# USB3.net
KiCad netlist of a schematic drawn in Altium Designer
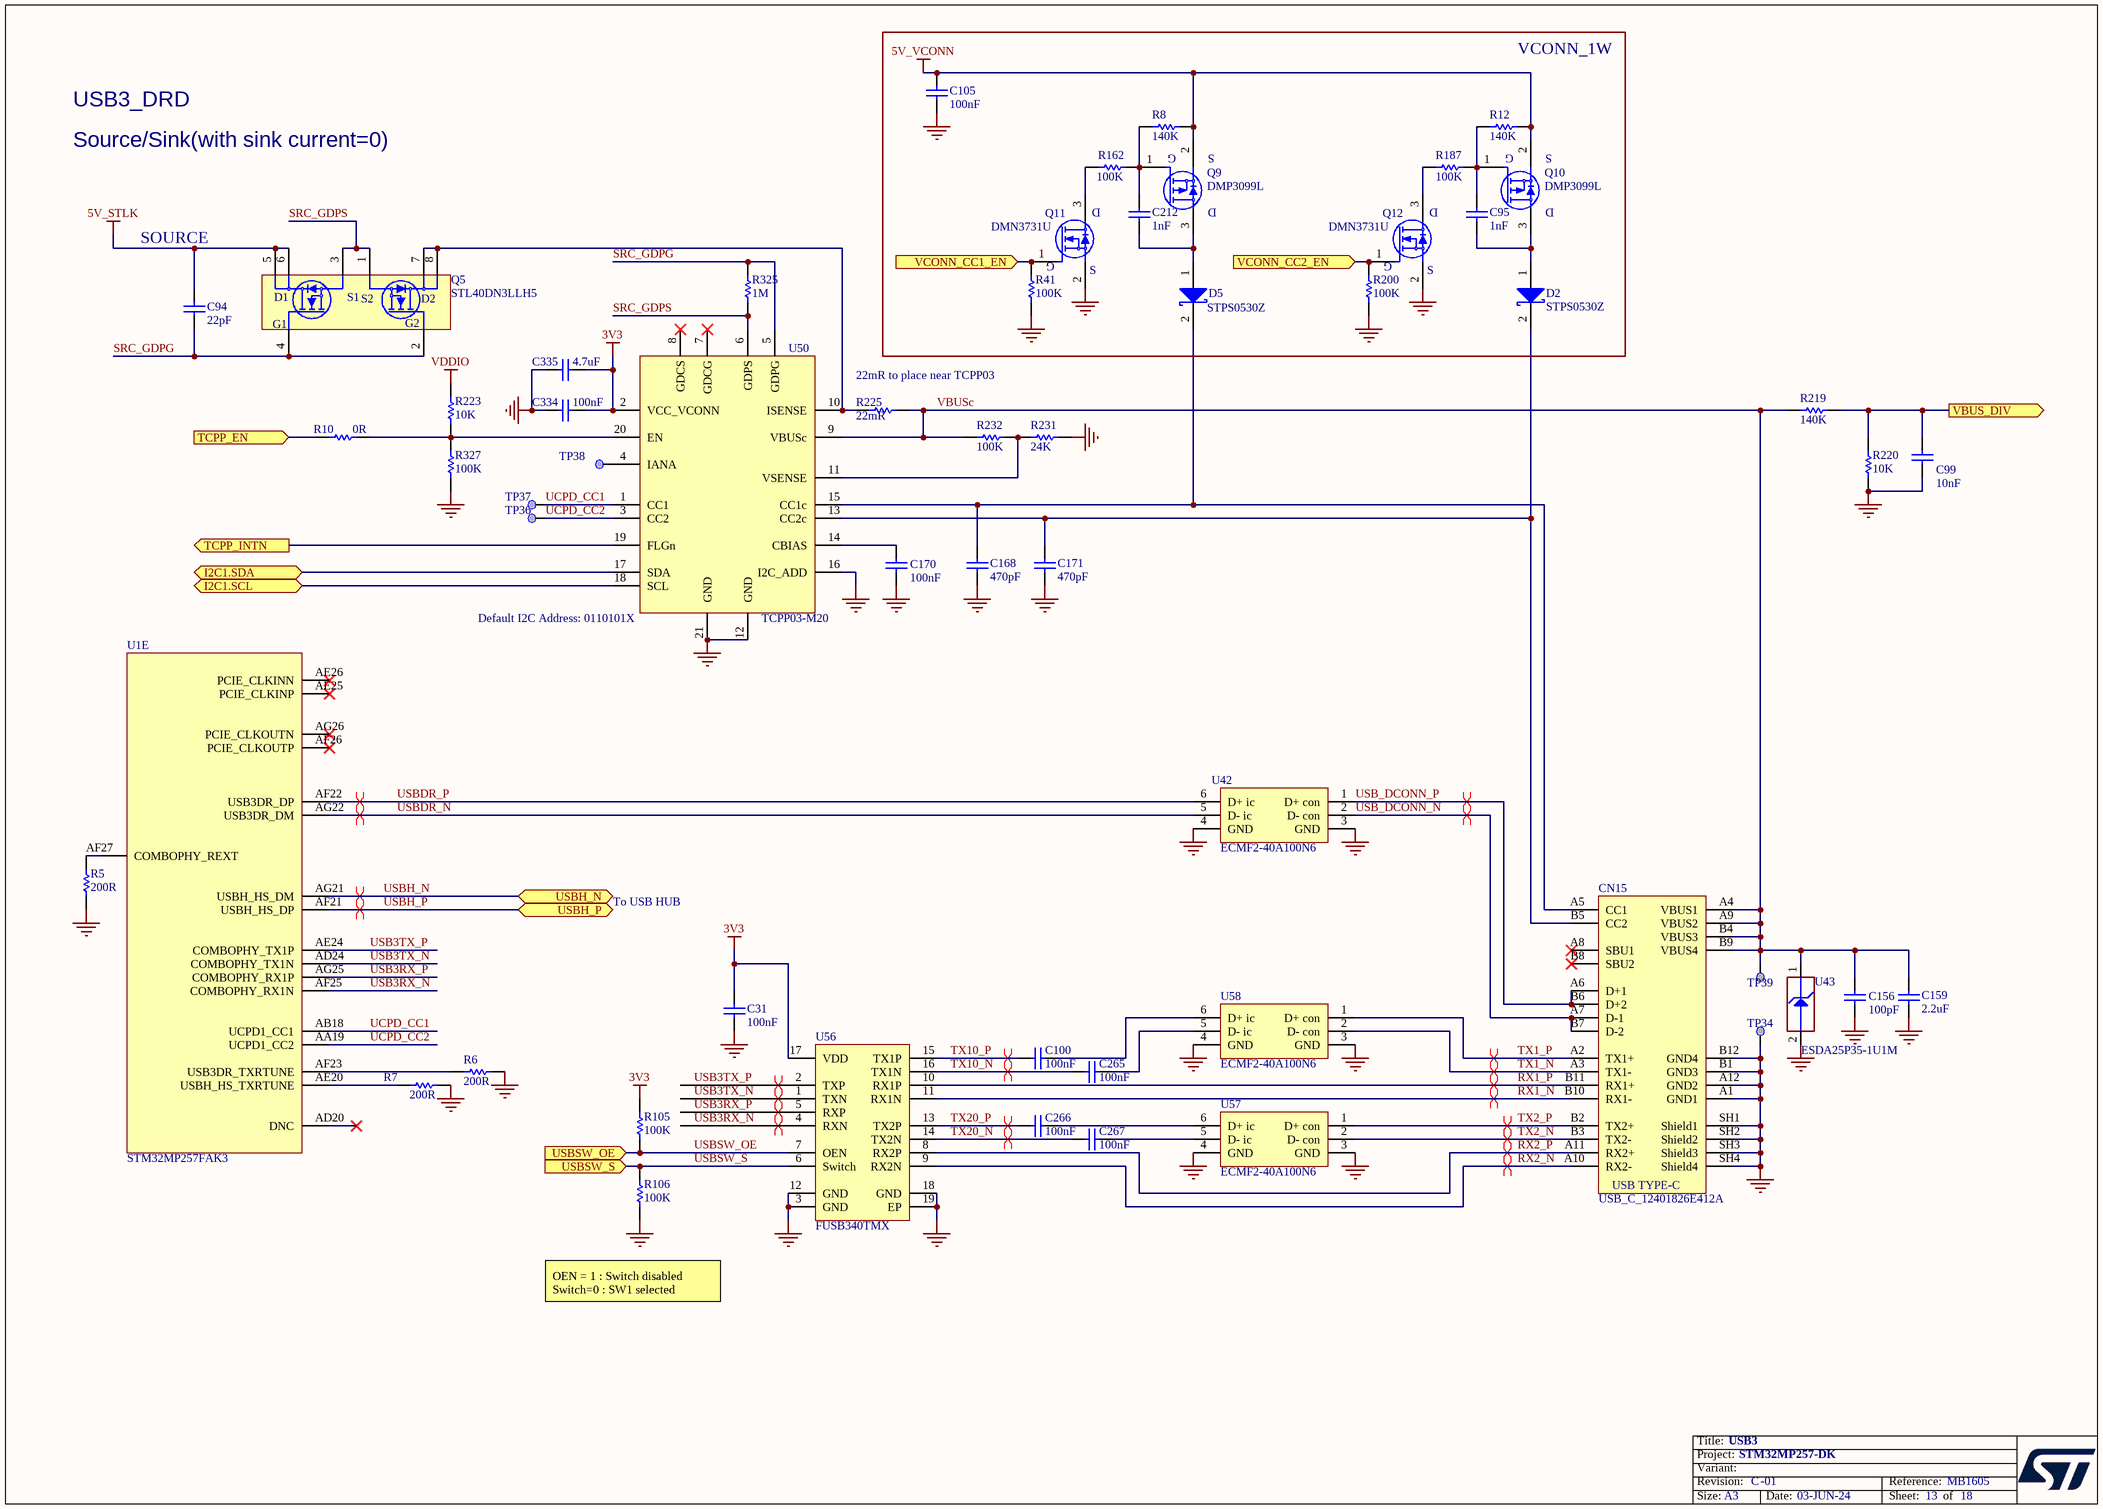
[diagram p0: USB3.SchDoc]

(export (version "E")
  (design (tool "Eeschema 10.0.6"))
  (components
    (comp (ref "C31")
      (value "100nF")
      (footprint "C0402")
      (description "Capacitor, MLCC, 100nF, 16V, X7R, +/-10%, 0402, T=0.5mm")
      (fields (field (name "INTERNAL_PART_NUMBER") "MCD-00006") (field (name "MANUFACTURER") "YAGEO"))
      (libsource (lib "MCD_PARTS_database") (part "Capacitor"))
    )
    (comp (ref "C94")
      (value "22pF")
      (footprint "C0402")
      (description "Capacitor, MLCC, 22pF, 50V, C0G, +/-5%, 0402, T=0.5mm")
      (fields (field (name "INTERNAL_PART_NUMBER") "MCD-01995") (field (name "MANUFACTURER") "TDK"))
      (libsource (lib "MCD_PARTS_database") (part "Capacitor"))
    )
    (comp (ref "C95")
      (value "1nF")
      (footprint "C0402")
      (description "Capacitor, MLCC, 1nF, 16V, X7R, +/-10%, 0402, T=0.5mm")
      (fields (field (name "INTERNAL_PART_NUMBER") "MCD-00198") (field (name "MANUFACTURER") "YAGEO"))
      (libsource (lib "MCD_PARTS_database") (part "Capacitor"))
    )
    (comp (ref "C99")
      (value "10nF")
      (footprint "C0402")
      (description "Capacitor, MLCC, 10nF, 16V, X7R, 10%, 0402, T=0.5mm")
      (fields
        (field (name "INTERNAL_PART_NUMBER") "MCD-00011")
        (field (name "MANUFACTURER_PART_NUMBER") "CC0402KRX7R7BB103")
        (field (name "PROVIDED_BY") "SUBCO")
      )
      (libsource (lib "MCD_PARTS_database") (part "Capacitor"))
    )
    (comp (ref "C100")
      (value "100nF")
      (footprint "C0201_H0P3")
      (description "Capacitor, MLCC, 100nF,10V, X5R, +/-10%, 0201, T=0.3mm")
      (fields (field (name "INTERNAL_PART_NUMBER") "MCD-00697") (field (name "MANUFACTURER") "TDK"))
      (libsource (lib "MCD_PARTS_database") (part "Capacitor"))
    )
    (comp (ref "C105")
      (value "100nF")
      (footprint "C0402")
      (description "Capacitor, MLCC, 100nF, 16V, X7R, +/-10%, 0402, T=0.5mm")
      (fields (field (name "INTERNAL_PART_NUMBER") "MCD-00006") (field (name "MANUFACTURER") "YAGEO"))
      (libsource (lib "MCD_PARTS_database") (part "Capacitor"))
    )
    (comp (ref "C156")
      (value "100pF")
      (footprint "C0402")
      (description "Capacitor, MLCC, 100pF, 50V, NPO, +/-5%, 0402, T=0.5mm")
      (fields
        (field (name "INTERNAL_PART_NUMBER") "MCD-00205")
        (field (name "MANUFACTURER_PART_NUMBER") "CC0402JRNPO9BN101")
      )
      (libsource (lib "MCD_PARTS_database") (part "Capacitor"))
    )
    (comp (ref "C159")
      (value "2.2uF")
      (footprint "C0805")
      (description "Capacitor, MLCC, 2.2uF, 25V, X7R, +/-10%, 0805, T=1,25mm")
      (fields (field (name "INTERNAL_PART_NUMBER") "MCD-02372") (field (name "MANUFACTURER") "MURATA"))
      (libsource (lib "MCD_PARTS_database") (part "Capacitor"))
    )
    (comp (ref "C168")
      (value "470pF")
      (footprint "C0402")
      (description "Capacitor, MLCC, 470pF, 50V, NPO, +/-5%, 0402, T=0.5mm")
      (fields
        (field (name "INTERNAL_PART_NUMBER") "MCD-00724")
        (field (name "MANUFACTURER_PART_NUMBER") "CC0402JRNPO9BN471")
      )
      (libsource (lib "MCD_PARTS_database") (part "Capacitor"))
    )
    (comp (ref "C170")
      (value "100nF")
      (footprint "C0603")
      (description "Capacitor, MLCC, 100nF, 50V, X7R, +/-10%, 0603, T=0.8mm")
      (fields (field (name "INTERNAL_PART_NUMBER") "MCD-01099") (field (name "BMS_PART_NUMBER") "9142278"))
      (libsource (lib "MCD_PARTS_database") (part "Capacitor"))
    )
    (comp (ref "C171")
      (value "470pF")
      (footprint "C0402")
      (description "Capacitor, MLCC, 470pF, 50V, NPO, +/-5%, 0402, T=0.5mm")
      (fields
        (field (name "INTERNAL_PART_NUMBER") "MCD-00724")
        (field (name "MANUFACTURER_PART_NUMBER") "CC0402JRNPO9BN471")
      )
      (libsource (lib "MCD_PARTS_database") (part "Capacitor"))
    )
    (comp (ref "C212")
      (value "1nF")
      (footprint "C0402")
      (description "Capacitor, MLCC, 1nF, 16V, X7R, +/-10%, 0402, T=0.5mm")
      (fields (field (name "INTERNAL_PART_NUMBER") "MCD-00198") (field (name "MANUFACTURER") "YAGEO"))
      (libsource (lib "MCD_PARTS_database") (part "Capacitor"))
    )
    (comp (ref "C265")
      (value "100nF")
      (footprint "C0201_H0P3")
      (description "Capacitor, MLCC, 100nF,10V, X5R, +/-10%, 0201, T=0.3mm")
      (fields (field (name "INTERNAL_PART_NUMBER") "MCD-00697") (field (name "MANUFACTURER") "TDK"))
      (libsource (lib "MCD_PARTS_database") (part "Capacitor"))
    )
    (comp (ref "C266")
      (value "100nF")
      (footprint "C0201_H0P3")
      (description "Capacitor, MLCC, 100nF,10V, X5R, +/-10%, 0201, T=0.3mm")
      (fields (field (name "INTERNAL_PART_NUMBER") "MCD-00697") (field (name "MANUFACTURER") "TDK"))
      (libsource (lib "MCD_PARTS_database") (part "Capacitor"))
    )
    (comp (ref "C267")
      (value "100nF")
      (footprint "C0201_H0P3")
      (description "Capacitor, MLCC, 100nF,10V, X5R, +/-10%, 0201, T=0.3mm")
      (fields (field (name "INTERNAL_PART_NUMBER") "MCD-00697") (field (name "MANUFACTURER") "TDK"))
      (libsource (lib "MCD_PARTS_database") (part "Capacitor"))
    )
    (comp (ref "C334")
      (value "100nF")
      (footprint "C0402")
      (description "Capacitor, MLCC, 100nF, 16V, X7R, +/-10%, 0402, T=0.5mm")
      (fields (field (name "INTERNAL_PART_NUMBER") "MCD-00006") (field (name "MANUFACTURER") "YAGEO"))
      (libsource (lib "MCD_PARTS_database") (part "Capacitor"))
    )
    (comp (ref "C335")
      (value "4.7uF")
      (footprint "C0402")
      (description "Capacitor, MLCC, 4.7uF, 6V3, X5R, +/-20%, 0402, T=0.5mm")
      (fields (field (name "INTERNAL_PART_NUMBER") "MCD-01356") (field (name "MANUFACTURER") "MURATA"))
      (libsource (lib "MCD_PARTS_database") (part "Capacitor"))
    )
    (comp (ref "CN15")
      (value "USB_C_12401826E412A")
      (footprint "CON_USB-TYPEC_AMPHENOL_12401826E412A")
      (description "USB_TypeC, 24 pins, RA, SMD, T=2.96mm (USB Certified 3.1)")
      (fields (field (name "INTERNAL_PART_NUMBER") "MCD-03232") (field (name "MANUFACTURER") "AMPHENOL ICC"))
      (libsource (lib "MCD_PARTS_database") (part "USB_TYPE_C_Receptacle"))
    )
    (comp (ref "D2")
      (value "STPS0530Z")
      (footprint "DIO_SOD123_1A_2K_H1P45")
      (description "Diode, Schottky, 0V33, 0.5A , 30V, SOD123")
      (fields
        (field (name "INTERNAL_PART_NUMBER") "MCD-03688")
        (field (name "MANUFACTURER") "STMICROELECTRONICS")
      )
      (libsource (lib "MCD_PARTS_database") (part "SCHOTTKY_1A_2K"))
    )
    (comp (ref "D5")
      (value "STPS0530Z")
      (footprint "DIO_SOD123_1A_2K_H1P45")
      (description "Diode, Schottky, 0V33, 0.5A , 30V, SOD123")
      (fields
        (field (name "INTERNAL_PART_NUMBER") "MCD-03688")
        (field (name "MANUFACTURER") "STMICROELECTRONICS")
      )
      (libsource (lib "MCD_PARTS_database") (part "SCHOTTKY_1A_2K"))
    )
    (comp (ref "Q5")
      (value "STL40DN3LLH5")
      (footprint "PowerFLAT_5x6")
      (description "MOSFET, Dual N-channel 30 V, 0.016 Ω typ., 40 A, STripFET™ H5 Power MOSFET")
      (fields
        (field (name "INTERNAL_PART_NUMBER") "MCD-02152")
        (field (name "MANUFACTURER") "STMICROELECTRONICS")
      )
      (libsource (lib "MCD_PARTS_database") (part "STL40DN3LLH5"))
    )
    (comp (ref "Q9")
      (value "DMP3099L")
      (footprint "MOS_SOT23")
      (description "Transistor, MOSFET, P-CH, 30V, 3.8A, SOT23")
      (fields
        (field (name "INTERNAL_PART_NUMBER") "MCD-03690")
        (field (name "MANUFACTURER") "DIODES INCORPORATED")
      )
      (libsource (lib "MCD_PARTS_database") (part "MOSFET_P-CHANNEL"))
    )
    (comp (ref "Q10")
      (value "DMP3099L")
      (footprint "MOS_SOT23")
      (description "Transistor, MOSFET, P-CH, 30V, 3.8A, SOT23")
      (fields
        (field (name "INTERNAL_PART_NUMBER") "MCD-03690")
        (field (name "MANUFACTURER") "DIODES INCORPORATED")
      )
      (libsource (lib "MCD_PARTS_database") (part "MOSFET_P-CHANNEL"))
    )
    (comp (ref "Q11")
      (value "DMN3731U")
      (footprint "MOS_SOT23")
      (description "Transistor, MOSFET, N-CH, 30V, 0.9A, SOT23")
      (fields
        (field (name "INTERNAL_PART_NUMBER") "MCD-03691")
        (field (name "MANUFACTURER") "DIODES INCORPORATED")
      )
      (libsource (lib "MCD_PARTS_database") (part "MOSFET_N-CHANNEL"))
    )
    (comp (ref "Q12")
      (value "DMN3731U")
      (footprint "MOS_SOT23")
      (description "Transistor, MOSFET, N-CH, 30V, 0.9A, SOT23")
      (fields
        (field (name "INTERNAL_PART_NUMBER") "MCD-03691")
        (field (name "MANUFACTURER") "DIODES INCORPORATED")
      )
      (libsource (lib "MCD_PARTS_database") (part "MOSFET_N-CHANNEL"))
    )
    (comp (ref "R5")
      (value "200R")
      (footprint "R0402")
      (description "Resistor, 200R, 0402, +/-1%, 1/16W")
      (fields (field (name "INTERNAL_PART_NUMBER") "MCD-00417") (field (name "MANUFACTURER") "YAGEO"))
      (libsource (lib "MCD_PARTS_database") (part "Resistor"))
    )
    (comp (ref "R6")
      (value "200R")
      (footprint "R0402")
      (description "Resistor, 200R, 0402, +/-1%, 1/16W")
      (fields (field (name "INTERNAL_PART_NUMBER") "MCD-00417") (field (name "MANUFACTURER") "YAGEO"))
      (libsource (lib "MCD_PARTS_database") (part "Resistor"))
    )
    (comp (ref "R7")
      (value "200R")
      (footprint "R0402")
      (description "Resistor, 200R, 0402, +/-1%, 1/16W")
      (fields (field (name "INTERNAL_PART_NUMBER") "MCD-00417") (field (name "MANUFACTURER") "YAGEO"))
      (libsource (lib "MCD_PARTS_database") (part "Resistor"))
    )
    (comp (ref "R8")
      (value "140K")
      (footprint "R0402")
      (description "Resistor, 140K, 0402, +/-1%, 1/16W")
      (fields (field (name "INTERNAL_PART_NUMBER") "MCD-02335") (field (name "MANUFACTURER") "YAGEO"))
      (libsource (lib "MCD_PARTS_database") (part "Resistor"))
    )
    (comp (ref "R10")
      (value "0R")
      (footprint "R0402")
      (description "Resistor,0R,0402,5%,1/16W")
      (fields
        (field (name "INTERNAL_PART_NUMBER") "MCD-00052")
        (field (name "MANUFACTURER_PART_NUMBER") "RC0402JR-070RL")
      )
      (libsource (lib "MCD_PARTS_database") (part "Resistor"))
    )
    (comp (ref "R12")
      (value "140K")
      (footprint "R0402")
      (description "Resistor, 140K, 0402, +/-1%, 1/16W")
      (fields (field (name "INTERNAL_PART_NUMBER") "MCD-02335") (field (name "MANUFACTURER") "YAGEO"))
      (libsource (lib "MCD_PARTS_database") (part "Resistor"))
    )
    (comp (ref "R41")
      (value "100K")
      (footprint "R0402")
      (description "Resistor, 100K, 0402, +/-1%, 1/16W")
      (fields (field (name "INTERNAL_PART_NUMBER") "MCD-00059") (field (name "MANUFACTURER") "YAGEO"))
      (libsource (lib "MCD_PARTS_database") (part "Resistor"))
    )
    (comp (ref "R105")
      (value "100K")
      (footprint "R0402")
      (description "Resistor,100K,0402,1%,1/16W")
      (fields (field (name "INTERNAL_PART_NUMBER") "MCD-00059") (field (name "MANUFACTURER") "YAGEO"))
      (libsource (lib "MCD_PARTS_database") (part "Resistor"))
    )
    (comp (ref "R106")
      (value "100K")
      (footprint "R0402")
      (description "Resistor,100K,0402,1%,1/16W")
      (fields (field (name "INTERNAL_PART_NUMBER") "MCD-00059") (field (name "MANUFACTURER") "YAGEO"))
      (libsource (lib "MCD_PARTS_database") (part "Resistor"))
    )
    (comp (ref "R162")
      (value "100K")
      (footprint "R0402")
      (description "Resistor, 100K, 0402, +/-1%, 1/16W")
      (fields (field (name "INTERNAL_PART_NUMBER") "MCD-00059") (field (name "MANUFACTURER") "YAGEO"))
      (libsource (lib "MCD_PARTS_database") (part "Resistor"))
    )
    (comp (ref "R187")
      (value "100K")
      (footprint "R0402")
      (description "Resistor, 100K, 0402, +/-1%, 1/16W")
      (fields (field (name "INTERNAL_PART_NUMBER") "MCD-00059") (field (name "MANUFACTURER") "YAGEO"))
      (libsource (lib "MCD_PARTS_database") (part "Resistor"))
    )
    (comp (ref "R200")
      (value "100K")
      (footprint "R0402")
      (description "Resistor, 100K, 0402, +/-1%, 1/16W")
      (fields (field (name "INTERNAL_PART_NUMBER") "MCD-00059") (field (name "MANUFACTURER") "YAGEO"))
      (libsource (lib "MCD_PARTS_database") (part "Resistor"))
    )
    (comp (ref "R219")
      (value "140K")
      (footprint "R0402")
      (description "Resistor, 140K, 0402, +/-1%, 1/16W")
      (fields (field (name "INTERNAL_PART_NUMBER") "MCD-02335") (field (name "MANUFACTURER") "YAGEO"))
      (libsource (lib "MCD_PARTS_database") (part "Resistor"))
    )
    (comp (ref "R220")
      (value "10K")
      (footprint "R0402")
      (description "Resistor, 10K, 0402, +/-1%, 1/16W")
      (fields (field (name "INTERNAL_PART_NUMBER") "MCD-00053") (field (name "BMS_PART_NUMBER") "9131590"))
      (libsource (lib "MCD_PARTS_database") (part "Resistor"))
    )
    (comp (ref "R223")
      (value "10K")
      (footprint "R0402")
      (description "Resistor, 10K, 0402, +/-1%, 1/16W")
      (fields (field (name "INTERNAL_PART_NUMBER") "MCD-00053") (field (name "BMS_PART_NUMBER") "9131590"))
      (libsource (lib "MCD_PARTS_database") (part "Resistor"))
    )
    (comp (ref "R225")
      (value "22mR")
      (footprint "R0603")
      (description "Resistor, 22mR, 0603, +/-1%, 1/3W")
      (fields (field (name "INTERNAL_PART_NUMBER") "MCD-02232") (field (name "MANUFACTURER") "PANASONIC"))
      (libsource (lib "MCD_PARTS_database") (part "Resistor"))
    )
    (comp (ref "R231")
      (value "24K")
      (footprint "R0402")
      (description "Resistor, 24K, 0402, +/-1%, 1/16W")
      (fields (field (name "INTERNAL_PART_NUMBER") "MCD-00435") (field (name "MANUFACTURER") "YAGEO"))
      (libsource (lib "MCD_PARTS_database") (part "Resistor"))
    )
    (comp (ref "R232")
      (value "100K")
      (footprint "R0402")
      (description "Resistor,100K,0402,0.5%,1/16W")
      (fields (field (name "INTERNAL_PART_NUMBER") "MCD-02265") (field (name "MANUFACTURER") "YAGEO"))
      (libsource (lib "MCD_PARTS_database") (part "Resistor"))
    )
    (comp (ref "R325")
      (value "1M")
      (footprint "R0402")
      (description "Resistor, 1M, 0402, +/-1%, 1/16W")
      (fields (field (name "INTERNAL_PART_NUMBER") "MCD-00182") (field (name "BMS_PART_NUMBER") "9131778"))
      (libsource (lib "MCD_PARTS_database") (part "Resistor"))
    )
    (comp (ref "R327")
      (value "100K")
      (footprint "R0402")
      (description "Resistor,100K,0402,0.5%,1/16W")
      (fields (field (name "INTERNAL_PART_NUMBER") "MCD-02265") (field (name "MANUFACTURER") "YAGEO"))
      (libsource (lib "MCD_PARTS_database") (part "Resistor"))
    )
    (comp (ref "TP34")
      (value "Test Point")
      (footprint "TP_SMD_1MM")
      (description "Test Point 1mm")
      (fields
        (field (name "INTERNAL_PART_NUMBER") "MCD-00074")
        (field (name "MANUFACTURER_PART_NUMBER") "n/a")
      )
      (libsource (lib "") (part "Test Point_2"))
    )
    (comp (ref "TP36")
      (value "Test Point")
      (footprint "TP_SMD_1MM")
      (description "Test Point 1mm")
      (fields
        (field (name "INTERNAL_PART_NUMBER") "MCD-00074")
        (field (name "MANUFACTURER_PART_NUMBER") "n/a")
      )
      (libsource (lib "MCD_PARTS_database") (part "Test Point"))
    )
    (comp (ref "TP37")
      (value "Test Point")
      (footprint "TP_SMD_1MM")
      (description "Test Point 1mm")
      (fields
        (field (name "INTERNAL_PART_NUMBER") "MCD-00074")
        (field (name "MANUFACTURER_PART_NUMBER") "n/a")
      )
      (libsource (lib "MCD_PARTS_database") (part "Test Point"))
    )
    (comp (ref "TP38")
      (value "Test Point")
      (footprint "TP_SMD_1MM")
      (description "Test Point 1mm")
      (fields
        (field (name "INTERNAL_PART_NUMBER") "MCD-00074")
        (field (name "MANUFACTURER_PART_NUMBER") "n/a")
      )
      (libsource (lib "MCD_PARTS_database") (part "Test Point"))
    )
    (comp (ref "TP39")
      (value "Test Point")
      (footprint "TP_SMD_1MM")
      (description "Test Point 1mm")
      (fields
        (field (name "INTERNAL_PART_NUMBER") "MCD-00074")
        (field (name "MANUFACTURER_PART_NUMBER") "n/a")
      )
      (libsource (lib "") (part "Test Point_1"))
    )
    (comp (ref "U1")
      (value "STM32MP257FAK3")
      (footprint "ICC_TFBGA424_14X14_P050_H1P20_CODE-B0A2")
      (description "MPU , 2xCortex-A35@1.5GHz, Cortex-M33@400MHz, TFBGA 14x14, pitch 0.5, 648KB SRAM, With Crypto")
      (fields
        (field (name "INTERNAL_PART_NUMBER") "MCD-03375")
        (field (name "MANUFACTURER") "STMICROELECTRONICS")
      )
      (libsource (lib "MCD_PARTS_database") (part "STM32MP257FAK3"))
    )
    (comp (ref "U42")
      (value "ECMF2-40A100N6")
      (footprint "ESD_UQFN-6L_1P45X1P4_P040")
      (description "ESD protection & Common Filter High Speed serial Interfaces , 0.4 pitch")
      (fields
        (field (name "INTERNAL_PART_NUMBER") "MCD-03060")
        (field (name "MANUFACTURER") "STMICROELECTRONICS")
      )
      (libsource (lib "MCD_PARTS_database") (part "ECMF2-40A100N6"))
    )
    (comp (ref "U43")
      (value "ESDA25P35-1U1M")
      (footprint "ESD_QFN1610_2N_1K_2A")
      (description "High power Transient voltage suppressor:25V/35A EOS and ESD transients protection.")
      (fields (field (name "INTERNAL_PART_NUMBER") "MCD-01207") (field (name "BMS_PART_NUMBER") "9179045"))
      (libsource (lib "MCD_PARTS_database") (part "ESD-TRANSIL"))
    )
    (comp (ref "U50")
      (value "TCPP03-M20")
      (footprint "ICC_QFN20-EPAD_4X4_P050")
      (description "USB Type-C Port Protection for USB DRP Power Delivery, PPS compliant")
      (fields
        (field (name "INTERNAL_PART_NUMBER") "MCD-02130")
        (field (name "MANUFACTURER") "STMICROELECTRONICS")
      )
      (libsource (lib "MCD_PARTS_database") (part "TCPP03-M20"))
    )
    (comp (ref "U56")
      (value "FUSB340TMX")
      (footprint "ICC_UQFN18-EPAD_2X2P80_P040")
      (description "Switch USB3.1 Superspeed 10 Gbps , Gen1 and Gen2")
      (fields
        (field (name "INTERNAL_PART_NUMBER") "MCD-02300")
        (field (name "MANUFACTURER") "ON SEMICONDUCTOR")
      )
      (libsource (lib "MCD_PARTS_database") (part "FUSB340TMX"))
    )
    (comp (ref "U57")
      (value "ECMF2-40A100N6")
      (footprint "ESD_UQFN-6L_1P45X1P4_P040")
      (description "IC, ESD protection and Common Filter High Speed serial Interfaces, 10.7 GHz")
      (fields
        (field (name "INTERNAL_PART_NUMBER") "MCD-03060")
        (field (name "MANUFACTURER") "STMICROELECTRONICS")
      )
      (libsource (lib "MCD_PARTS_database") (part "ECMF2-40A100N6"))
    )
    (comp (ref "U58")
      (value "ECMF2-40A100N6")
      (footprint "ESD_UQFN-6L_1P45X1P4_P040")
      (description "IC, ESD protection and Common Filter High Speed serial Interfaces, 10.7 GHz")
      (fields
        (field (name "INTERNAL_PART_NUMBER") "MCD-03060")
        (field (name "MANUFACTURER") "STMICROELECTRONICS")
      )
      (libsource (lib "MCD_PARTS_database") (part "ECMF2-40A100N6"))
    )
  )
  (nets
    (net (code "1") (name "/I2C1.SCL") (class "Default")
      (node (ref "U50") (pin "18") (pinfunction "SCL_18") (pintype "passive"))
    )
    (net (code "2") (name "/I2C1.SDA") (class "Default")
      (node (ref "U50") (pin "17") (pinfunction "SDA_17") (pintype "passive"))
    )
    (net (code "3") (name "/RX1_N") (class "Default")
      (node (ref "CN15") (pin "B10") (pinfunction "RX1-_B10") (pintype "passive"))
      (node (ref "U56") (pin "11") (pinfunction "RX1N_11") (pintype "passive"))
    )
    (net (code "4") (name "/RX1_P") (class "Default")
      (node (ref "CN15") (pin "B11") (pinfunction "RX1+_B11") (pintype "passive"))
      (node (ref "U56") (pin "10") (pinfunction "RX1P_10") (pintype "passive"))
    )
    (net (code "5") (name "/RX2_N") (class "Default")
      (node (ref "CN15") (pin "A10") (pinfunction "RX2-_A10") (pintype "passive"))
      (node (ref "U56") (pin "9") (pinfunction "RX2N_9") (pintype "passive"))
    )
    (net (code "6") (name "/RX2_P") (class "Default")
      (node (ref "CN15") (pin "A11") (pinfunction "RX2+_A11") (pintype "passive"))
      (node (ref "U56") (pin "8") (pinfunction "RX2P_8") (pintype "passive"))
    )
    (net (code "7") (name "/SRC_GDPG") (class "Default")
      (node (ref "C94") (pin "1") (pinfunction "1_1") (pintype "passive"))
      (node (ref "Q5") (pin "2") (pinfunction "G2_2") (pintype "passive"))
      (node (ref "Q5") (pin "4") (pinfunction "G1_4") (pintype "passive"))
      (node (ref "R325") (pin "2") (pinfunction "2_2") (pintype "passive"))
      (node (ref "U50") (pin "5") (pinfunction "GDPG_5") (pintype "passive"))
    )
    (net (code "8") (name "/SRC_GDPS") (class "Default")
      (node (ref "Q5") (pin "1") (pinfunction "S2_1") (pintype "passive"))
      (node (ref "Q5") (pin "3") (pinfunction "S1_3") (pintype "passive"))
      (node (ref "R325") (pin "1") (pinfunction "1_1") (pintype "passive"))
      (node (ref "U50") (pin "6") (pinfunction "GDPS_6") (pintype "passive"))
    )
    (net (code "9") (name "/TCPP_EN") (class "Default")
      (node (ref "R10") (pin "1") (pinfunction "1_1") (pintype "passive"))
    )
    (net (code "10") (name "/TCPP_INTN") (class "Default")
      (node (ref "U50") (pin "19") (pinfunction "FLGn_19") (pintype "passive"))
    )
    (net (code "11") (name "/TX1_N") (class "Default")
      (node (ref "CN15") (pin "A3") (pinfunction "TX1-_A3") (pintype "passive"))
      (node (ref "U58") (pin "2") (pinfunction "D-_con_2") (pintype "passive"))
    )
    (net (code "12") (name "/TX1_P") (class "Default")
      (node (ref "CN15") (pin "A2") (pinfunction "TX1+_A2") (pintype "passive"))
      (node (ref "U58") (pin "1") (pinfunction "D+_con_1") (pintype "passive"))
    )
    (net (code "13") (name "/TX2_N") (class "Default")
      (node (ref "CN15") (pin "B3") (pinfunction "TX2-_B3") (pintype "passive"))
      (node (ref "U57") (pin "2") (pinfunction "D-_con_2") (pintype "passive"))
    )
    (net (code "14") (name "/TX2_P") (class "Default")
      (node (ref "CN15") (pin "B2") (pinfunction "TX2+_B2") (pintype "passive"))
      (node (ref "U57") (pin "1") (pinfunction "D+_con_1") (pintype "passive"))
    )
    (net (code "15") (name "/TX10_N") (class "Default")
      (node (ref "C265") (pin "1") (pinfunction "1_1") (pintype "passive"))
      (node (ref "U56") (pin "16") (pinfunction "TX1N_16") (pintype "passive"))
    )
    (net (code "16") (name "/TX10_P") (class "Default")
      (node (ref "C100") (pin "1") (pinfunction "1_1") (pintype "passive"))
      (node (ref "U56") (pin "15") (pinfunction "TX1P_15") (pintype "passive"))
    )
    (net (code "17") (name "/TX20_N") (class "Default")
      (node (ref "C267") (pin "1") (pinfunction "1_1") (pintype "passive"))
      (node (ref "U56") (pin "14") (pinfunction "TX2N_14") (pintype "passive"))
    )
    (net (code "18") (name "/TX20_P") (class "Default")
      (node (ref "C266") (pin "1") (pinfunction "1_1") (pintype "passive"))
      (node (ref "U56") (pin "13") (pinfunction "TX2P_13") (pintype "passive"))
    )
    (net (code "19") (name "/UCPD_CC1") (class "Default")
      (node (ref "TP37") (pin "1") (pinfunction "1_1") (pintype "passive"))
      (node (ref "U1") (pin "AB18") (pinfunction "UCPD1_CC1_AB18") (pintype "passive"))
      (node (ref "U50") (pin "1") (pinfunction "CC1_1") (pintype "passive"))
    )
    (net (code "20") (name "/UCPD_CC2") (class "Default")
      (node (ref "TP36") (pin "1") (pinfunction "1_1") (pintype "passive"))
      (node (ref "U1") (pin "AA19") (pinfunction "UCPD1_CC2_AA19") (pintype "passive"))
      (node (ref "U50") (pin "3") (pinfunction "CC2_3") (pintype "passive"))
    )
    (net (code "21") (name "/USB3RX_N") (class "Default")
      (node (ref "U1") (pin "AF25") (pinfunction "COMBOPHY_RX1N_AF25") (pintype "passive"))
      (node (ref "U56") (pin "4") (pinfunction "RXN_4") (pintype "passive"))
    )
    (net (code "22") (name "/USB3RX_P") (class "Default")
      (node (ref "U1") (pin "AG25") (pinfunction "COMBOPHY_RX1P_AG25") (pintype "passive"))
      (node (ref "U56") (pin "5") (pinfunction "RXP_5") (pintype "passive"))
    )
    (net (code "23") (name "/USB3TX_N") (class "Default")
      (node (ref "U1") (pin "AD24") (pinfunction "COMBOPHY_TX1N_AD24") (pintype "passive"))
      (node (ref "U56") (pin "1") (pinfunction "TXN_1") (pintype "passive"))
    )
    (net (code "24") (name "/USB3TX_P") (class "Default")
      (node (ref "U1") (pin "AE24") (pinfunction "COMBOPHY_TX1P_AE24") (pintype "passive"))
      (node (ref "U56") (pin "2") (pinfunction "TXP_2") (pintype "passive"))
    )
    (net (code "25") (name "/USBDR_N") (class "Default")
      (node (ref "U1") (pin "AG22") (pinfunction "USB3DR_DM_AG22") (pintype "passive"))
      (node (ref "U42") (pin "5") (pinfunction "D-_ic_5") (pintype "passive"))
    )
    (net (code "26") (name "/USBDR_P") (class "Default")
      (node (ref "U1") (pin "AF22") (pinfunction "USB3DR_DP_AF22") (pintype "passive"))
      (node (ref "U42") (pin "6") (pinfunction "D+_ic_6") (pintype "passive"))
    )
    (net (code "27") (name "/USBH_N") (class "Default")
      (node (ref "U1") (pin "AG21") (pinfunction "USBH_HS_DM_AG21") (pintype "passive"))
    )
    (net (code "28") (name "/USBH_P") (class "Default")
      (node (ref "U1") (pin "AF21") (pinfunction "USBH_HS_DP_AF21") (pintype "passive"))
    )
    (net (code "29") (name "/USBSW_OE") (class "Default")
      (node (ref "R105") (pin "1") (pinfunction "1_1") (pintype "passive"))
      (node (ref "U56") (pin "7") (pinfunction "OEN_7") (pintype "passive"))
    )
    (net (code "30") (name "/USBSW_S") (class "Default")
      (node (ref "R106") (pin "2") (pinfunction "2_2") (pintype "passive"))
      (node (ref "U56") (pin "6") (pinfunction "Switch_6") (pintype "passive"))
    )
    (net (code "31") (name "/USB_DCONN_N") (class "Default")
      (node (ref "CN15") (pin "A7") (pinfunction "D-1_A7") (pintype "passive"))
      (node (ref "CN15") (pin "B7") (pinfunction "D-2_B7") (pintype "passive"))
      (node (ref "U42") (pin "2") (pinfunction "D-_con_2") (pintype "passive"))
    )
    (net (code "32") (name "/USB_DCONN_P") (class "Default")
      (node (ref "CN15") (pin "A6") (pinfunction "D+1_A6") (pintype "passive"))
      (node (ref "CN15") (pin "B6") (pinfunction "D+2_B6") (pintype "passive"))
      (node (ref "U42") (pin "1") (pinfunction "D+_con_1") (pintype "passive"))
    )
    (net (code "33") (name "/VBUS_DIV") (class "Default")
      (node (ref "C99") (pin "1") (pinfunction "1_1") (pintype "passive"))
      (node (ref "R219") (pin "1") (pinfunction "1_1") (pintype "passive"))
      (node (ref "R220") (pin "2") (pinfunction "2_2") (pintype "passive"))
    )
    (net (code "34") (name "/VBUSc") (class "Default")
      (node (ref "C156") (pin "2") (pinfunction "2_2") (pintype "passive"))
      (node (ref "C159") (pin "2") (pinfunction "2_2") (pintype "passive"))
      (node (ref "CN15") (pin "A4") (pinfunction "VBUS1_A4") (pintype "passive"))
      (node (ref "CN15") (pin "A9") (pinfunction "VBUS2_A9") (pintype "passive"))
      (node (ref "CN15") (pin "B4") (pinfunction "VBUS3_B4") (pintype "passive"))
      (node (ref "CN15") (pin "B9") (pinfunction "VBUS4_B9") (pintype "passive"))
      (node (ref "R219") (pin "2") (pinfunction "2_2") (pintype "passive"))
      (node (ref "R225") (pin "1") (pinfunction "1_1") (pintype "passive"))
      (node (ref "R232") (pin "1") (pinfunction "1_1") (pintype "passive"))
      (node (ref "TP39") (pin "1") (pinfunction "1_1") (pintype "passive"))
      (node (ref "U43") (pin "1") (pinfunction "IO1_1") (pintype "passive"))
      (node (ref "U50") (pin "9") (pinfunction "VBUSc_9") (pintype "passive"))
    )
    (net (code "35") (name "/VCONN_CC1_EN") (class "Default")
      (node (ref "Q11") (pin "1") (pinfunction "G_1") (pintype "passive"))
      (node (ref "R41") (pin "2") (pinfunction "2_2") (pintype "passive"))
    )
    (net (code "36") (name "/VCONN_CC2_EN") (class "Default")
      (node (ref "Q12") (pin "1") (pinfunction "G_1") (pintype "passive"))
      (node (ref "R200") (pin "2") (pinfunction "2_2") (pintype "passive"))
    )
    (net (code "37") (name "3V3") (class "Default")
      (node (ref "C31") (pin "1") (pinfunction "1_1") (pintype "passive"))
      (node (ref "C334") (pin "1") (pinfunction "1_1") (pintype "passive"))
      (node (ref "C335") (pin "1") (pinfunction "1_1") (pintype "passive"))
      (node (ref "R105") (pin "2") (pinfunction "2_2") (pintype "passive"))
      (node (ref "U50") (pin "2") (pinfunction "VCC_VCONN_2") (pintype "passive"))
      (node (ref "U56") (pin "17") (pinfunction "VDD_17") (pintype "passive"))
    )
    (net (code "38") (name "5V_STLK") (class "Default")
      (node (ref "C94") (pin "2") (pinfunction "2_2") (pintype "passive"))
      (node (ref "Q5") (pin "5") (pinfunction "D1_5") (pintype "passive"))
      (node (ref "Q5") (pin "6") (pinfunction "D1_6") (pintype "passive"))
    )
    (net (code "39") (name "5V_VCONN") (class "Default")
      (node (ref "C105") (pin "1") (pinfunction "1_1") (pintype "passive"))
      (node (ref "Q10") (pin "2") (pinfunction "S_2") (pintype "passive"))
      (node (ref "Q9") (pin "2") (pinfunction "S_2") (pintype "passive"))
      (node (ref "R12") (pin "2") (pinfunction "2_2") (pintype "passive"))
      (node (ref "R8") (pin "2") (pinfunction "2_2") (pintype "passive"))
    )
    (net (code "40") (name "GND") (class "Default")
      (node (ref "C105") (pin "2") (pinfunction "2_2") (pintype "passive"))
      (node (ref "C156") (pin "1") (pinfunction "1_1") (pintype "passive"))
      (node (ref "C159") (pin "1") (pinfunction "1_1") (pintype "passive"))
      (node (ref "C168") (pin "1") (pinfunction "1_1") (pintype "passive"))
      (node (ref "C170") (pin "1") (pinfunction "1_1") (pintype "passive"))
      (node (ref "C171") (pin "1") (pinfunction "1_1") (pintype "passive"))
      (node (ref "C31") (pin "2") (pinfunction "2_2") (pintype "passive"))
      (node (ref "C334") (pin "2") (pinfunction "2_2") (pintype "passive"))
      (node (ref "C335") (pin "2") (pinfunction "2_2") (pintype "passive"))
      (node (ref "C99") (pin "2") (pinfunction "2_2") (pintype "passive"))
      (node (ref "CN15") (pin "A1") (pinfunction "GND1_A1") (pintype "passive"))
      (node (ref "CN15") (pin "A12") (pinfunction "GND2_A12") (pintype "passive"))
      (node (ref "CN15") (pin "B1") (pinfunction "GND3_B1") (pintype "passive"))
      (node (ref "CN15") (pin "B12") (pinfunction "GND4_B12") (pintype "passive"))
      (node (ref "CN15") (pin "SH1") (pinfunction "Shield1_SH1") (pintype "passive"))
      (node (ref "CN15") (pin "SH2") (pinfunction "Shield2_SH2") (pintype "passive"))
      (node (ref "CN15") (pin "SH3") (pinfunction "Shield3_SH3") (pintype "passive"))
      (node (ref "CN15") (pin "SH4") (pinfunction "Shield4_SH4") (pintype "passive"))
      (node (ref "Q11") (pin "2") (pinfunction "S_2") (pintype "passive"))
      (node (ref "Q12") (pin "2") (pinfunction "S_2") (pintype "passive"))
      (node (ref "R106") (pin "1") (pinfunction "1_1") (pintype "passive"))
      (node (ref "R200") (pin "1") (pinfunction "1_1") (pintype "passive"))
      (node (ref "R220") (pin "1") (pinfunction "1_1") (pintype "passive"))
      (node (ref "R231") (pin "2") (pinfunction "2_2") (pintype "passive"))
      (node (ref "R327") (pin "1") (pinfunction "1_1") (pintype "passive"))
      (node (ref "R41") (pin "1") (pinfunction "1_1") (pintype "passive"))
      (node (ref "R5") (pin "1") (pinfunction "1_1") (pintype "passive"))
      (node (ref "R6") (pin "2") (pinfunction "2_2") (pintype "passive"))
      (node (ref "R7") (pin "2") (pinfunction "2_2") (pintype "passive"))
      (node (ref "TP34") (pin "1") (pinfunction "1_1") (pintype "passive"))
      (node (ref "U42") (pin "3") (pinfunction "GND_3") (pintype "passive"))
      (node (ref "U42") (pin "4") (pinfunction "GND_4") (pintype "passive"))
      (node (ref "U43") (pin "2") (pinfunction "GND_2") (pintype "passive"))
      (node (ref "U50") (pin "12") (pinfunction "GND_12") (pintype "passive"))
      (node (ref "U50") (pin "16") (pinfunction "I2C_ADD_16") (pintype "passive"))
      (node (ref "U50") (pin "21") (pinfunction "GND_21") (pintype "passive"))
      (node (ref "U56") (pin "12") (pinfunction "GND_12") (pintype "passive"))
      (node (ref "U56") (pin "18") (pinfunction "GND_18") (pintype "passive"))
      (node (ref "U56") (pin "19") (pinfunction "EP_19") (pintype "passive"))
      (node (ref "U56") (pin "3") (pinfunction "GND_3") (pintype "passive"))
      (node (ref "U57") (pin "3") (pinfunction "GND_3") (pintype "passive"))
      (node (ref "U57") (pin "4") (pinfunction "GND_4") (pintype "passive"))
      (node (ref "U58") (pin "3") (pinfunction "GND_3") (pintype "passive"))
      (node (ref "U58") (pin "4") (pinfunction "GND_4") (pintype "passive"))
    )
    (net (code "41") (name "Net-(CN15-CC1)") (class "Default")
      (node (ref "C168") (pin "2") (pinfunction "2_2") (pintype "passive"))
      (node (ref "CN15") (pin "A5") (pinfunction "CC1_A5") (pintype "passive"))
      (node (ref "D5") (pin "2") (pinfunction "K_2") (pintype "passive"))
      (node (ref "U50") (pin "15") (pinfunction "CC1c_15") (pintype "passive"))
    )
    (net (code "42") (name "Net-(CN15-CC2)") (class "Default")
      (node (ref "C171") (pin "2") (pinfunction "2_2") (pintype "passive"))
      (node (ref "CN15") (pin "B5") (pinfunction "CC2_B5") (pintype "passive"))
      (node (ref "D2") (pin "2") (pinfunction "K_2") (pintype "passive"))
      (node (ref "U50") (pin "13") (pinfunction "CC2c_13") (pintype "passive"))
    )
    (net (code "43") (name "Net-(D2-A)") (class "Default")
      (node (ref "C95") (pin "1") (pinfunction "1_1") (pintype "passive"))
      (node (ref "D2") (pin "1") (pinfunction "A_1") (pintype "passive"))
      (node (ref "Q10") (pin "3") (pinfunction "D_3") (pintype "passive"))
    )
    (net (code "44") (name "Net-(D5-A)") (class "Default")
      (node (ref "C212") (pin "1") (pinfunction "1_1") (pintype "passive"))
      (node (ref "D5") (pin "1") (pinfunction "A_1") (pintype "passive"))
      (node (ref "Q9") (pin "3") (pinfunction "D_3") (pintype "passive"))
    )
    (net (code "45") (name "Net-(Q9-G)") (class "Default")
      (node (ref "C212") (pin "2") (pinfunction "2_2") (pintype "passive"))
      (node (ref "Q9") (pin "1") (pinfunction "G_1") (pintype "passive"))
      (node (ref "R162") (pin "2") (pinfunction "2_2") (pintype "passive"))
      (node (ref "R8") (pin "1") (pinfunction "1_1") (pintype "passive"))
    )
    (net (code "46") (name "Net-(Q10-G)") (class "Default")
      (node (ref "C95") (pin "2") (pinfunction "2_2") (pintype "passive"))
      (node (ref "Q10") (pin "1") (pinfunction "G_1") (pintype "passive"))
      (node (ref "R12") (pin "1") (pinfunction "1_1") (pintype "passive"))
      (node (ref "R187") (pin "2") (pinfunction "2_2") (pintype "passive"))
    )
    (net (code "47") (name "Net-(Q11-D)") (class "Default")
      (node (ref "Q11") (pin "3") (pinfunction "D_3") (pintype "passive"))
      (node (ref "R162") (pin "1") (pinfunction "1_1") (pintype "passive"))
    )
    (net (code "48") (name "Net-(Q12-D)") (class "Default")
      (node (ref "Q12") (pin "3") (pinfunction "D_3") (pintype "passive"))
      (node (ref "R187") (pin "1") (pinfunction "1_1") (pintype "passive"))
    )
    (net (code "49") (name "Net-(U1E-COMBOPHY_REXT)") (class "Default")
      (node (ref "R5") (pin "2") (pinfunction "2_2") (pintype "passive"))
      (node (ref "U1") (pin "AF27") (pinfunction "COMBOPHY_REXT_AF27") (pintype "passive"))
    )
    (net (code "50") (name "Net-(U1E-USB3DR_TXRTUNE)") (class "Default")
      (node (ref "R6") (pin "1") (pinfunction "1_1") (pintype "passive"))
      (node (ref "U1") (pin "AF23") (pinfunction "USB3DR_TXRTUNE_AF23") (pintype "passive"))
    )
    (net (code "51") (name "Net-(U1E-USBH_HS_TXRTUNE)") (class "Default")
      (node (ref "R7") (pin "1") (pinfunction "1_1") (pintype "passive"))
      (node (ref "U1") (pin "AE20") (pinfunction "USBH_HS_TXRTUNE_AE20") (pintype "passive"))
    )
    (net (code "52") (name "Net-(U50-CBIAS)") (class "Default")
      (node (ref "C170") (pin "2") (pinfunction "2_2") (pintype "passive"))
      (node (ref "U50") (pin "14") (pinfunction "CBIAS_14") (pintype "passive"))
    )
    (net (code "53") (name "Net-(U50-EN)") (class "Default")
      (node (ref "R10") (pin "2") (pinfunction "2_2") (pintype "passive"))
      (node (ref "R223") (pin "1") (pinfunction "1_1") (pintype "passive"))
      (node (ref "R327") (pin "2") (pinfunction "2_2") (pintype "passive"))
      (node (ref "U50") (pin "20") (pinfunction "EN_20") (pintype "passive"))
    )
    (net (code "54") (name "Net-(U50-IANA)") (class "Default")
      (node (ref "TP38") (pin "1") (pinfunction "1_1") (pintype "passive"))
      (node (ref "U50") (pin "4") (pinfunction "IANA_4") (pintype "passive"))
    )
    (net (code "55") (name "Net-(U50-ISENSE)") (class "Default")
      (node (ref "Q5") (pin "7") (pinfunction "D2_7") (pintype "passive"))
      (node (ref "Q5") (pin "8") (pinfunction "D2_8") (pintype "passive"))
      (node (ref "R225") (pin "2") (pinfunction "2_2") (pintype "passive"))
      (node (ref "U50") (pin "10") (pinfunction "ISENSE_10") (pintype "passive"))
    )
    (net (code "56") (name "Net-(U50-VSENSE)") (class "Default")
      (node (ref "R231") (pin "1") (pinfunction "1_1") (pintype "passive"))
      (node (ref "R232") (pin "2") (pinfunction "2_2") (pintype "passive"))
      (node (ref "U50") (pin "11") (pinfunction "VSENSE_11") (pintype "passive"))
    )
    (net (code "57") (name "Net-(U57-D+_ic)") (class "Default")
      (node (ref "C266") (pin "2") (pinfunction "2_2") (pintype "passive"))
      (node (ref "U57") (pin "6") (pinfunction "D+_ic_6") (pintype "passive"))
    )
    (net (code "58") (name "Net-(U57-D-_ic)") (class "Default")
      (node (ref "C267") (pin "2") (pinfunction "2_2") (pintype "passive"))
      (node (ref "U57") (pin "5") (pinfunction "D-_ic_5") (pintype "passive"))
    )
    (net (code "59") (name "Net-(U58-D+_ic)") (class "Default")
      (node (ref "C100") (pin "2") (pinfunction "2_2") (pintype "passive"))
      (node (ref "U58") (pin "6") (pinfunction "D+_ic_6") (pintype "passive"))
    )
    (net (code "60") (name "Net-(U58-D-_ic)") (class "Default")
      (node (ref "C265") (pin "2") (pinfunction "2_2") (pintype "passive"))
      (node (ref "U58") (pin "5") (pinfunction "D-_ic_5") (pintype "passive"))
    )
    (net (code "61") (name "VDDIO") (class "Default")
      (node (ref "R223") (pin "2") (pinfunction "2_2") (pintype "passive"))
    )
    (net (code "62") (name "unconnected-(CN15-SBU1-PadA8)") (class "Default")
      (node (ref "CN15") (pin "A8") (pinfunction "SBU1_A8") (pintype "passive+no_connect"))
    )
    (net (code "63") (name "unconnected-(CN15-SBU2-PadB8)") (class "Default")
      (node (ref "CN15") (pin "B8") (pinfunction "SBU2_B8") (pintype "passive+no_connect"))
    )
    (net (code "64") (name "unconnected-(U1E-DNC-PadAD20)") (class "Default")
      (node (ref "U1") (pin "AD20") (pinfunction "DNC_AD20") (pintype "passive+no_connect"))
    )
    (net (code "65") (name "unconnected-(U1E-PCIE_CLKINN-PadAE26)") (class "Default")
      (node (ref "U1") (pin "AE26") (pinfunction "PCIE_CLKINN_AE26") (pintype "passive+no_connect"))
    )
    (net (code "66") (name "unconnected-(U1E-PCIE_CLKINP-PadAE25)") (class "Default")
      (node (ref "U1") (pin "AE25") (pinfunction "PCIE_CLKINP_AE25") (pintype "passive+no_connect"))
    )
    (net (code "67") (name "unconnected-(U1E-PCIE_CLKOUTN-PadAG26)") (class "Default")
      (node (ref "U1") (pin "AG26") (pinfunction "PCIE_CLKOUTN_AG26") (pintype "passive+no_connect"))
    )
    (net (code "68") (name "unconnected-(U1E-PCIE_CLKOUTP-PadAF26)") (class "Default")
      (node (ref "U1") (pin "AF26") (pinfunction "PCIE_CLKOUTP_AF26") (pintype "passive+no_connect"))
    )
    (net (code "69") (name "unconnected-(U50-GDCG-Pad7)") (class "Default")
      (node (ref "U50") (pin "7") (pinfunction "GDCG_7") (pintype "passive+no_connect"))
    )
    (net (code "70") (name "unconnected-(U50-GDCS-Pad8)") (class "Default")
      (node (ref "U50") (pin "8") (pinfunction "GDCS_8") (pintype "passive+no_connect"))
    )
  )
)
